# GrandBoard.net
KiCad netlist of a schematic drawn in EAGLE
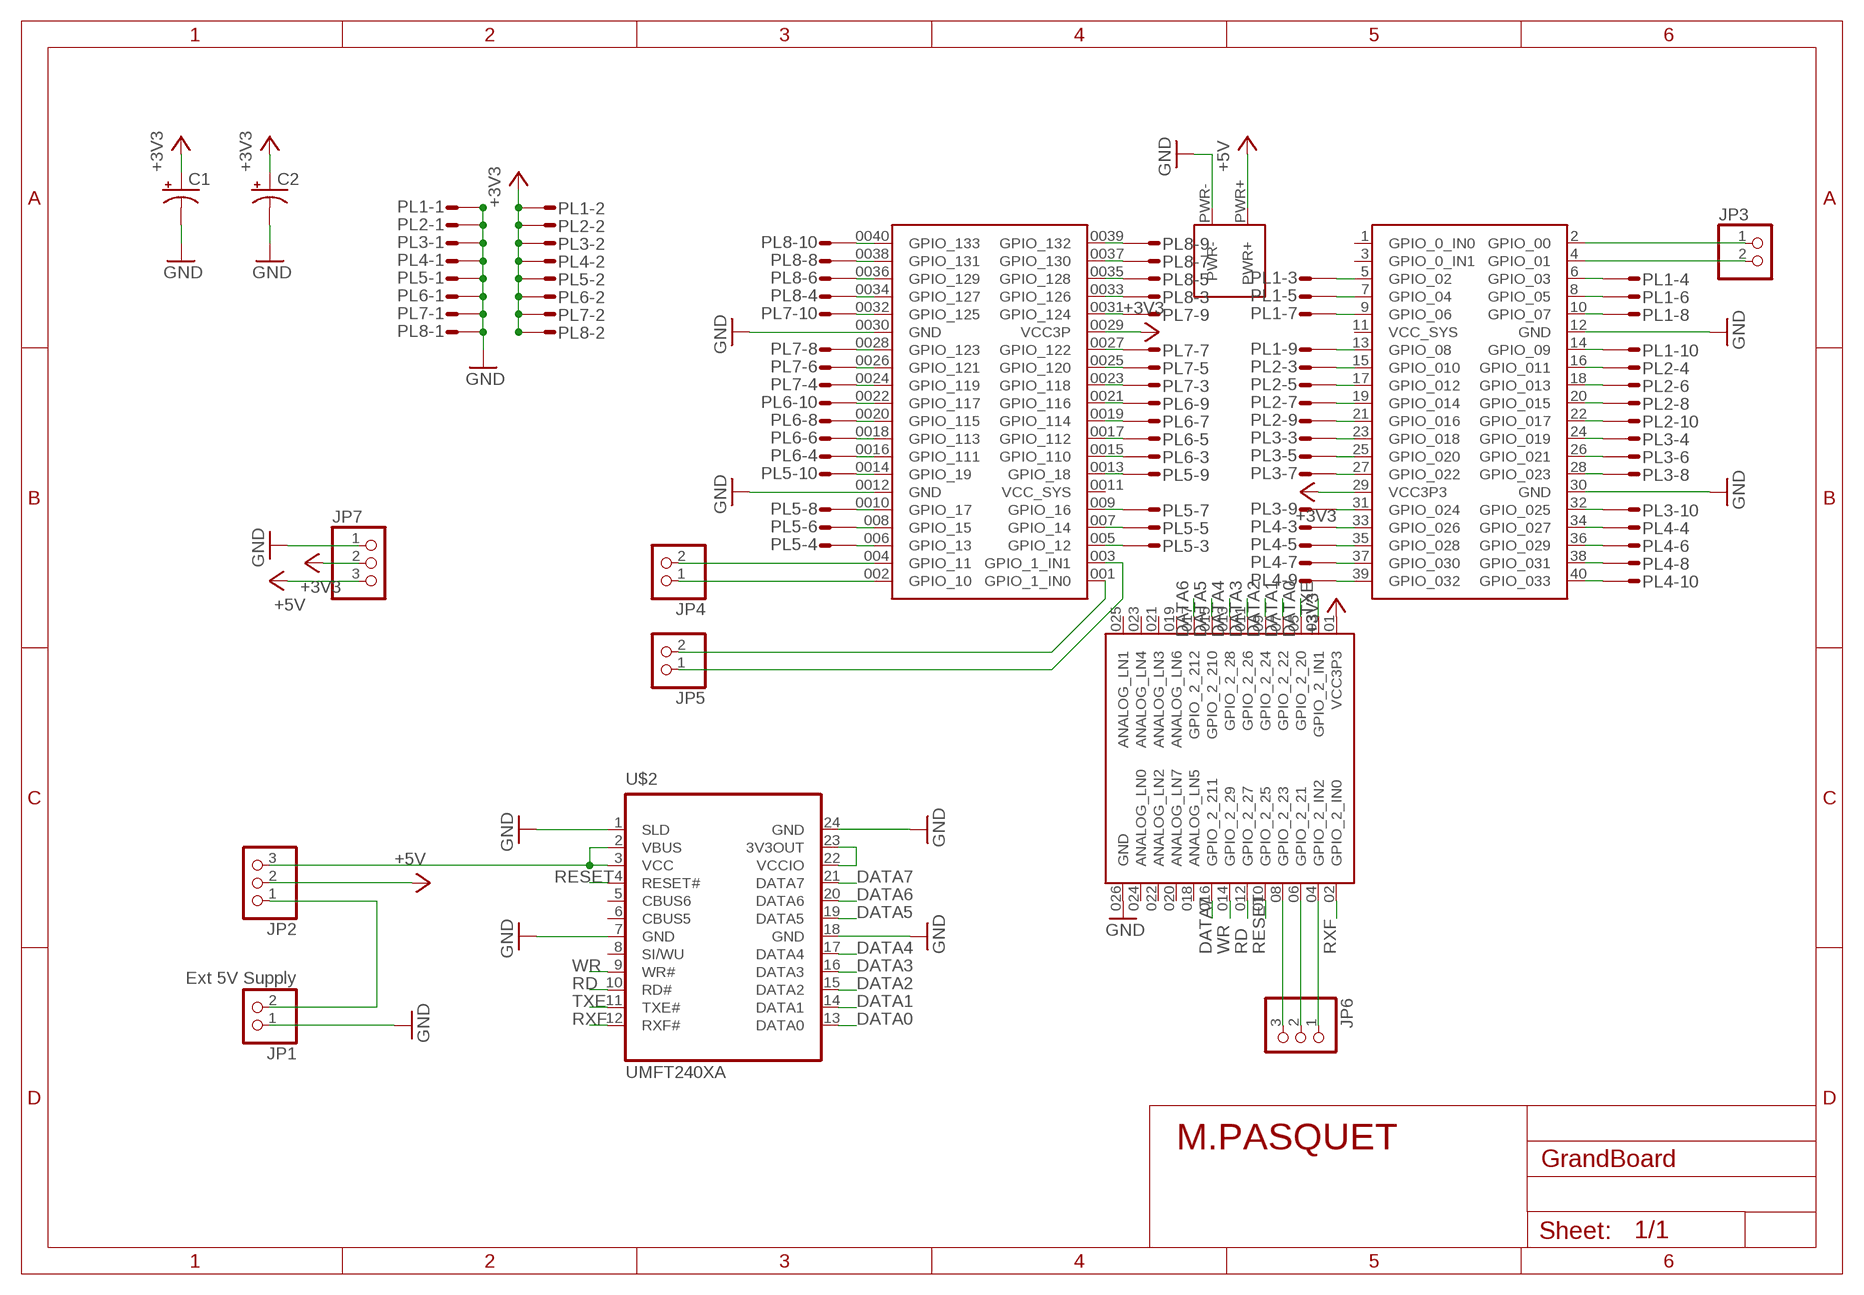
[diagram p0: schematic, sheet 1]

(export (version "E")
  (design (tool "Eeschema 10.0.6"))
  (components
    (comp (ref "C1")
      (value "CAP_POLPTH2")
      (footprint "eagle-import:CPOL-RADIAL-10UF-25V")
      (libsource (lib "eagle-import") (part "CAP_POLPTH2"))
    )
    (comp (ref "C2")
      (value "CAP_POLPTH2")
      (footprint "eagle-import:CPOL-RADIAL-10UF-25V")
      (libsource (lib "eagle-import") (part "CAP_POLPTH2"))
    )
    (comp (ref "JP1")
      (value "Ext 5V Supply")
      (footprint "eagle-import:1X02")
      (libsource (lib "eagle-import") (part "PINHD-1X2"))
    )
    (comp (ref "JP2")
      (value "PINHD-1X3")
      (footprint "eagle-import:1X03")
      (libsource (lib "eagle-import") (part "PINHD-1X3"))
    )
    (comp (ref "JP3")
      (value "PINHD-1X2")
      (footprint "eagle-import:1X02")
      (libsource (lib "eagle-import") (part "PINHD-1X2"))
    )
    (comp (ref "JP4")
      (value "PINHD-1X2")
      (footprint "eagle-import:1X02")
      (libsource (lib "eagle-import") (part "PINHD-1X2"))
    )
    (comp (ref "JP5")
      (value "PINHD-1X2")
      (footprint "eagle-import:1X02")
      (libsource (lib "eagle-import") (part "PINHD-1X2"))
    )
    (comp (ref "JP6")
      (value "PINHD-1X3")
      (footprint "eagle-import:1X03")
      (libsource (lib "eagle-import") (part "PINHD-1X3"))
    )
    (comp (ref "JP7")
      (value "PINHD-1X3")
      (footprint "eagle-import:1X03")
      (libsource (lib "eagle-import") (part "PINHD-1X3"))
    )
    (comp (ref "PL1")
      (value "10HS")
      (footprint "eagle-import:10H")
      (libsource (lib "eagle-import") (part "10HS"))
    )
    (comp (ref "PL2")
      (value "10HS")
      (footprint "eagle-import:10H")
      (libsource (lib "eagle-import") (part "10HS"))
    )
    (comp (ref "PL3")
      (value "10HS")
      (footprint "eagle-import:10H")
      (libsource (lib "eagle-import") (part "10HS"))
    )
    (comp (ref "PL4")
      (value "10HS")
      (footprint "eagle-import:10H")
      (libsource (lib "eagle-import") (part "10HS"))
    )
    (comp (ref "PL5")
      (value "10HS")
      (footprint "eagle-import:10H")
      (libsource (lib "eagle-import") (part "10HS"))
    )
    (comp (ref "PL6")
      (value "10HS")
      (footprint "eagle-import:10H")
      (libsource (lib "eagle-import") (part "10HS"))
    )
    (comp (ref "PL7")
      (value "10HS")
      (footprint "eagle-import:10H")
      (libsource (lib "eagle-import") (part "10HS"))
    )
    (comp (ref "PL8")
      (value "10HS")
      (footprint "eagle-import:10H")
      (libsource (lib "eagle-import") (part "10HS"))
    )
    (comp (ref "U$1")
      (value "DE0-NANO")
      (footprint "eagle-import:DE0-NANO")
      (libsource (lib "eagle-import") (part "DE0-NANO"))
    )
    (comp (ref "U$2")
      (value "UMFT240XA")
      (footprint "eagle-import:UMFT240XA")
      (libsource (lib "eagle-import") (part "UMFT240XA"))
    )
  )
  (nets
    (net (code "1") (name "+3V3") (class "Default")
      (node (ref "C1") (pin "1") (pinfunction "+_1") (pintype "passive"))
      (node (ref "C2") (pin "1") (pinfunction "+_1") (pintype "passive"))
      (node (ref "JP7") (pin "2") (pinfunction "2_2") (pintype "passive"))
      (node (ref "PL1") (pin "2") (pinfunction "S_2") (pintype "passive"))
      (node (ref "PL2") (pin "2") (pinfunction "S_2") (pintype "passive"))
      (node (ref "PL3") (pin "2") (pinfunction "S_2") (pintype "passive"))
      (node (ref "PL4") (pin "2") (pinfunction "S_2") (pintype "passive"))
      (node (ref "PL5") (pin "2") (pinfunction "S_2") (pintype "passive"))
      (node (ref "PL6") (pin "2") (pinfunction "S_2") (pintype "passive"))
      (node (ref "PL7") (pin "2") (pinfunction "S_2") (pintype "passive"))
      (node (ref "PL8") (pin "2") (pinfunction "S_2") (pintype "passive"))
      (node (ref "U$1") (pin "0029") (pinfunction "VCC3P_0029") (pintype "bidirectional"))
      (node (ref "U$1") (pin "01") (pinfunction "VCC3P3_01") (pintype "bidirectional"))
      (node (ref "U$1") (pin "29") (pinfunction "VCC3P3_29") (pintype "bidirectional"))
    )
    (net (code "2") (name "+5V") (class "Default")
      (node (ref "JP2") (pin "2") (pinfunction "2_2") (pintype "passive"))
      (node (ref "JP7") (pin "3") (pinfunction "3_3") (pintype "passive"))
      (node (ref "U$1") (pin "PWR+") (pinfunction "PWR+_PWR+") (pintype "bidirectional"))
    )
    (net (code "3") (name "/DATA0") (class "Default")
      (node (ref "U$1") (pin "05") (pinfunction "GPIO_2_20_05") (pintype "bidirectional"))
      (node (ref "U$2") (pin "13") (pinfunction "DATA0_13") (pintype "input"))
    )
    (net (code "4") (name "/DATA1") (class "Default")
      (node (ref "U$1") (pin "07") (pinfunction "GPIO_2_22_07") (pintype "bidirectional"))
      (node (ref "U$2") (pin "14") (pinfunction "DATA1_14") (pintype "input"))
    )
    (net (code "5") (name "/DATA2") (class "Default")
      (node (ref "U$1") (pin "09") (pinfunction "GPIO_2_24_09") (pintype "bidirectional"))
      (node (ref "U$2") (pin "15") (pinfunction "DATA2_15") (pintype "input"))
    )
    (net (code "6") (name "/DATA3") (class "Default")
      (node (ref "U$1") (pin "011") (pinfunction "GPIO_2_26_011") (pintype "bidirectional"))
      (node (ref "U$2") (pin "16") (pinfunction "DATA3_16") (pintype "input"))
    )
    (net (code "7") (name "/DATA4") (class "Default")
      (node (ref "U$1") (pin "013") (pinfunction "GPIO_2_28_013") (pintype "bidirectional"))
      (node (ref "U$2") (pin "17") (pinfunction "DATA4_17") (pintype "input"))
    )
    (net (code "8") (name "/DATA5") (class "Default")
      (node (ref "U$1") (pin "015") (pinfunction "GPIO_2_210_015") (pintype "bidirectional"))
      (node (ref "U$2") (pin "19") (pinfunction "DATA5_19") (pintype "input"))
    )
    (net (code "9") (name "/DATA6") (class "Default")
      (node (ref "U$1") (pin "017") (pinfunction "GPIO_2_212_017") (pintype "bidirectional"))
      (node (ref "U$2") (pin "20") (pinfunction "DATA6_20") (pintype "input"))
    )
    (net (code "10") (name "/DATA7") (class "Default")
      (node (ref "U$1") (pin "016") (pinfunction "GPIO_2_211_016") (pintype "bidirectional"))
      (node (ref "U$2") (pin "21") (pinfunction "DATA7_21") (pintype "input"))
    )
    (net (code "11") (name "/RD") (class "Default")
      (node (ref "U$1") (pin "012") (pinfunction "GPIO_2_27_012") (pintype "bidirectional"))
      (node (ref "U$2") (pin "10") (pinfunction "RD#_10") (pintype "input"))
    )
    (net (code "12") (name "/RESET") (class "Default")
      (node (ref "U$1") (pin "010") (pinfunction "GPIO_2_25_010") (pintype "bidirectional"))
      (node (ref "U$2") (pin "4") (pinfunction "RESET#_4") (pintype "input"))
    )
    (net (code "13") (name "/RXF") (class "Default")
      (node (ref "U$1") (pin "02") (pinfunction "GPIO_2_IN0_02") (pintype "bidirectional"))
      (node (ref "U$2") (pin "12") (pinfunction "RXF#_12") (pintype "input"))
    )
    (net (code "14") (name "/TXE") (class "Default")
      (node (ref "U$1") (pin "03") (pinfunction "GPIO_2_IN1_03") (pintype "bidirectional"))
      (node (ref "U$2") (pin "11") (pinfunction "TXE#_11") (pintype "input"))
    )
    (net (code "15") (name "/WR") (class "Default")
      (node (ref "U$1") (pin "014") (pinfunction "GPIO_2_29_014") (pintype "bidirectional"))
      (node (ref "U$2") (pin "9") (pinfunction "WR#_9") (pintype "input"))
    )
    (net (code "16") (name "GND") (class "Default")
      (node (ref "C1") (pin "2") (pinfunction "-_2") (pintype "passive"))
      (node (ref "C2") (pin "2") (pinfunction "-_2") (pintype "passive"))
      (node (ref "JP1") (pin "1") (pinfunction "1_1") (pintype "passive"))
      (node (ref "JP7") (pin "1") (pinfunction "1_1") (pintype "passive"))
      (node (ref "PL1") (pin "1") (pinfunction "S_1") (pintype "passive"))
      (node (ref "PL2") (pin "1") (pinfunction "S_1") (pintype "passive"))
      (node (ref "PL3") (pin "1") (pinfunction "S_1") (pintype "passive"))
      (node (ref "PL4") (pin "1") (pinfunction "S_1") (pintype "passive"))
      (node (ref "PL5") (pin "1") (pinfunction "S_1") (pintype "passive"))
      (node (ref "PL6") (pin "1") (pinfunction "S_1") (pintype "passive"))
      (node (ref "PL7") (pin "1") (pinfunction "S_1") (pintype "passive"))
      (node (ref "PL8") (pin "1") (pinfunction "S_1") (pintype "passive"))
      (node (ref "U$1") (pin "0012") (pinfunction "GND_0012") (pintype "bidirectional"))
      (node (ref "U$1") (pin "0030") (pinfunction "GND_0030") (pintype "bidirectional"))
      (node (ref "U$1") (pin "026") (pinfunction "GND_026") (pintype "bidirectional"))
      (node (ref "U$1") (pin "12") (pinfunction "GND_12") (pintype "bidirectional"))
      (node (ref "U$1") (pin "30") (pinfunction "GND_30") (pintype "bidirectional"))
      (node (ref "U$1") (pin "PWR-") (pinfunction "PWR-_PWR-") (pintype "bidirectional"))
      (node (ref "U$2") (pin "1") (pinfunction "SLD_1") (pintype "input"))
      (node (ref "U$2") (pin "18") (pinfunction "GND_18") (pintype "input"))
      (node (ref "U$2") (pin "24") (pinfunction "GND_24") (pintype "input"))
      (node (ref "U$2") (pin "7") (pinfunction "GND_7") (pintype "input"))
    )
    (net (code "17") (name "Net-(JP1-Pad2)") (class "Default")
      (node (ref "JP1") (pin "2") (pinfunction "2_2") (pintype "passive"))
      (node (ref "JP2") (pin "1") (pinfunction "1_1") (pintype "passive"))
    )
    (net (code "18") (name "Net-(PL1B-S)") (class "Default")
      (node (ref "PL1") (pin "10") (pinfunction "S_10") (pintype "passive"))
      (node (ref "U$1") (pin "14") (pinfunction "GPIO_09_14") (pintype "bidirectional"))
    )
    (net (code "19") (name "Net-(PL1D-S)") (class "Default")
      (node (ref "PL1") (pin "3") (pinfunction "S_3") (pintype "passive"))
      (node (ref "U$1") (pin "5") (pinfunction "GPIO_02_5") (pintype "bidirectional"))
    )
    (net (code "20") (name "Net-(PL1E-S)") (class "Default")
      (node (ref "PL1") (pin "4") (pinfunction "S_4") (pintype "passive"))
      (node (ref "U$1") (pin "6") (pinfunction "GPIO_03_6") (pintype "bidirectional"))
    )
    (net (code "21") (name "Net-(PL1F-S)") (class "Default")
      (node (ref "PL1") (pin "5") (pinfunction "S_5") (pintype "passive"))
      (node (ref "U$1") (pin "7") (pinfunction "GPIO_04_7") (pintype "bidirectional"))
    )
    (net (code "22") (name "Net-(PL1G-S)") (class "Default")
      (node (ref "PL1") (pin "6") (pinfunction "S_6") (pintype "passive"))
      (node (ref "U$1") (pin "8") (pinfunction "GPIO_05_8") (pintype "bidirectional"))
    )
    (net (code "23") (name "Net-(PL1H-S)") (class "Default")
      (node (ref "PL1") (pin "7") (pinfunction "S_7") (pintype "passive"))
      (node (ref "U$1") (pin "9") (pinfunction "GPIO_06_9") (pintype "bidirectional"))
    )
    (net (code "24") (name "Net-(PL1I-S)") (class "Default")
      (node (ref "PL1") (pin "8") (pinfunction "S_8") (pintype "passive"))
      (node (ref "U$1") (pin "10") (pinfunction "GPIO_07_10") (pintype "bidirectional"))
    )
    (net (code "25") (name "Net-(PL1J-S)") (class "Default")
      (node (ref "PL1") (pin "9") (pinfunction "S_9") (pintype "passive"))
      (node (ref "U$1") (pin "13") (pinfunction "GPIO_08_13") (pintype "bidirectional"))
    )
    (net (code "26") (name "Net-(PL2B-S)") (class "Default")
      (node (ref "PL2") (pin "10") (pinfunction "S_10") (pintype "passive"))
      (node (ref "U$1") (pin "22") (pinfunction "GPIO_017_22") (pintype "bidirectional"))
    )
    (net (code "27") (name "Net-(PL2D-S)") (class "Default")
      (node (ref "PL2") (pin "3") (pinfunction "S_3") (pintype "passive"))
      (node (ref "U$1") (pin "15") (pinfunction "GPIO_010_15") (pintype "bidirectional"))
    )
    (net (code "28") (name "Net-(PL2E-S)") (class "Default")
      (node (ref "PL2") (pin "4") (pinfunction "S_4") (pintype "passive"))
      (node (ref "U$1") (pin "16") (pinfunction "GPIO_011_16") (pintype "bidirectional"))
    )
    (net (code "29") (name "Net-(PL2F-S)") (class "Default")
      (node (ref "PL2") (pin "5") (pinfunction "S_5") (pintype "passive"))
      (node (ref "U$1") (pin "17") (pinfunction "GPIO_012_17") (pintype "bidirectional"))
    )
    (net (code "30") (name "Net-(PL2G-S)") (class "Default")
      (node (ref "PL2") (pin "6") (pinfunction "S_6") (pintype "passive"))
      (node (ref "U$1") (pin "18") (pinfunction "GPIO_013_18") (pintype "bidirectional"))
    )
    (net (code "31") (name "Net-(PL2H-S)") (class "Default")
      (node (ref "PL2") (pin "7") (pinfunction "S_7") (pintype "passive"))
      (node (ref "U$1") (pin "19") (pinfunction "GPIO_014_19") (pintype "bidirectional"))
    )
    (net (code "32") (name "Net-(PL2I-S)") (class "Default")
      (node (ref "PL2") (pin "8") (pinfunction "S_8") (pintype "passive"))
      (node (ref "U$1") (pin "20") (pinfunction "GPIO_015_20") (pintype "bidirectional"))
    )
    (net (code "33") (name "Net-(PL2J-S)") (class "Default")
      (node (ref "PL2") (pin "9") (pinfunction "S_9") (pintype "passive"))
      (node (ref "U$1") (pin "21") (pinfunction "GPIO_016_21") (pintype "bidirectional"))
    )
    (net (code "34") (name "Net-(PL3B-S)") (class "Default")
      (node (ref "PL3") (pin "10") (pinfunction "S_10") (pintype "passive"))
      (node (ref "U$1") (pin "32") (pinfunction "GPIO_025_32") (pintype "bidirectional"))
    )
    (net (code "35") (name "Net-(PL3D-S)") (class "Default")
      (node (ref "PL3") (pin "3") (pinfunction "S_3") (pintype "passive"))
      (node (ref "U$1") (pin "23") (pinfunction "GPIO_018_23") (pintype "bidirectional"))
    )
    (net (code "36") (name "Net-(PL3E-S)") (class "Default")
      (node (ref "PL3") (pin "4") (pinfunction "S_4") (pintype "passive"))
      (node (ref "U$1") (pin "24") (pinfunction "GPIO_019_24") (pintype "bidirectional"))
    )
    (net (code "37") (name "Net-(PL3F-S)") (class "Default")
      (node (ref "PL3") (pin "5") (pinfunction "S_5") (pintype "passive"))
      (node (ref "U$1") (pin "25") (pinfunction "GPIO_020_25") (pintype "bidirectional"))
    )
    (net (code "38") (name "Net-(PL3G-S)") (class "Default")
      (node (ref "PL3") (pin "6") (pinfunction "S_6") (pintype "passive"))
      (node (ref "U$1") (pin "26") (pinfunction "GPIO_021_26") (pintype "bidirectional"))
    )
    (net (code "39") (name "Net-(PL3H-S)") (class "Default")
      (node (ref "PL3") (pin "7") (pinfunction "S_7") (pintype "passive"))
      (node (ref "U$1") (pin "27") (pinfunction "GPIO_022_27") (pintype "bidirectional"))
    )
    (net (code "40") (name "Net-(PL3I-S)") (class "Default")
      (node (ref "PL3") (pin "8") (pinfunction "S_8") (pintype "passive"))
      (node (ref "U$1") (pin "28") (pinfunction "GPIO_023_28") (pintype "bidirectional"))
    )
    (net (code "41") (name "Net-(PL3J-S)") (class "Default")
      (node (ref "PL3") (pin "9") (pinfunction "S_9") (pintype "passive"))
      (node (ref "U$1") (pin "31") (pinfunction "GPIO_024_31") (pintype "bidirectional"))
    )
    (net (code "42") (name "Net-(PL4B-S)") (class "Default")
      (node (ref "PL4") (pin "10") (pinfunction "S_10") (pintype "passive"))
      (node (ref "U$1") (pin "40") (pinfunction "GPIO_033_40") (pintype "bidirectional"))
    )
    (net (code "43") (name "Net-(PL4D-S)") (class "Default")
      (node (ref "PL4") (pin "3") (pinfunction "S_3") (pintype "passive"))
      (node (ref "U$1") (pin "33") (pinfunction "GPIO_026_33") (pintype "bidirectional"))
    )
    (net (code "44") (name "Net-(PL4E-S)") (class "Default")
      (node (ref "PL4") (pin "4") (pinfunction "S_4") (pintype "passive"))
      (node (ref "U$1") (pin "34") (pinfunction "GPIO_027_34") (pintype "bidirectional"))
    )
    (net (code "45") (name "Net-(PL4F-S)") (class "Default")
      (node (ref "PL4") (pin "5") (pinfunction "S_5") (pintype "passive"))
      (node (ref "U$1") (pin "35") (pinfunction "GPIO_028_35") (pintype "bidirectional"))
    )
    (net (code "46") (name "Net-(PL4G-S)") (class "Default")
      (node (ref "PL4") (pin "6") (pinfunction "S_6") (pintype "passive"))
      (node (ref "U$1") (pin "36") (pinfunction "GPIO_029_36") (pintype "bidirectional"))
    )
    (net (code "47") (name "Net-(PL4H-S)") (class "Default")
      (node (ref "PL4") (pin "7") (pinfunction "S_7") (pintype "passive"))
      (node (ref "U$1") (pin "37") (pinfunction "GPIO_030_37") (pintype "bidirectional"))
    )
    (net (code "48") (name "Net-(PL4I-S)") (class "Default")
      (node (ref "PL4") (pin "8") (pinfunction "S_8") (pintype "passive"))
      (node (ref "U$1") (pin "38") (pinfunction "GPIO_031_38") (pintype "bidirectional"))
    )
    (net (code "49") (name "Net-(PL4J-S)") (class "Default")
      (node (ref "PL4") (pin "9") (pinfunction "S_9") (pintype "passive"))
      (node (ref "U$1") (pin "39") (pinfunction "GPIO_032_39") (pintype "bidirectional"))
    )
    (net (code "50") (name "Net-(PL5B-S)") (class "Default")
      (node (ref "PL5") (pin "10") (pinfunction "S_10") (pintype "passive"))
      (node (ref "U$1") (pin "0014") (pinfunction "GPIO_19_0014") (pintype "bidirectional"))
    )
    (net (code "51") (name "Net-(PL5D-S)") (class "Default")
      (node (ref "PL5") (pin "3") (pinfunction "S_3") (pintype "passive"))
      (node (ref "U$1") (pin "005") (pinfunction "GPIO_12_005") (pintype "bidirectional"))
    )
    (net (code "52") (name "Net-(PL5E-S)") (class "Default")
      (node (ref "PL5") (pin "4") (pinfunction "S_4") (pintype "passive"))
      (node (ref "U$1") (pin "006") (pinfunction "GPIO_13_006") (pintype "bidirectional"))
    )
    (net (code "53") (name "Net-(PL5F-S)") (class "Default")
      (node (ref "PL5") (pin "5") (pinfunction "S_5") (pintype "passive"))
      (node (ref "U$1") (pin "007") (pinfunction "GPIO_14_007") (pintype "bidirectional"))
    )
    (net (code "54") (name "Net-(PL5G-S)") (class "Default")
      (node (ref "PL5") (pin "6") (pinfunction "S_6") (pintype "passive"))
      (node (ref "U$1") (pin "008") (pinfunction "GPIO_15_008") (pintype "bidirectional"))
    )
    (net (code "55") (name "Net-(PL5H-S)") (class "Default")
      (node (ref "PL5") (pin "7") (pinfunction "S_7") (pintype "passive"))
      (node (ref "U$1") (pin "009") (pinfunction "GPIO_16_009") (pintype "bidirectional"))
    )
    (net (code "56") (name "Net-(PL5I-S)") (class "Default")
      (node (ref "PL5") (pin "8") (pinfunction "S_8") (pintype "passive"))
      (node (ref "U$1") (pin "0010") (pinfunction "GPIO_17_0010") (pintype "bidirectional"))
    )
    (net (code "57") (name "Net-(PL5J-S)") (class "Default")
      (node (ref "PL5") (pin "9") (pinfunction "S_9") (pintype "passive"))
      (node (ref "U$1") (pin "0013") (pinfunction "GPIO_18_0013") (pintype "bidirectional"))
    )
    (net (code "58") (name "Net-(PL6B-S)") (class "Default")
      (node (ref "PL6") (pin "10") (pinfunction "S_10") (pintype "passive"))
      (node (ref "U$1") (pin "0022") (pinfunction "GPIO_117_0022") (pintype "bidirectional"))
    )
    (net (code "59") (name "Net-(PL6D-S)") (class "Default")
      (node (ref "PL6") (pin "3") (pinfunction "S_3") (pintype "passive"))
      (node (ref "U$1") (pin "0015") (pinfunction "GPIO_110_0015") (pintype "bidirectional"))
    )
    (net (code "60") (name "Net-(PL6E-S)") (class "Default")
      (node (ref "PL6") (pin "4") (pinfunction "S_4") (pintype "passive"))
      (node (ref "U$1") (pin "0016") (pinfunction "GPIO_111_0016") (pintype "bidirectional"))
    )
    (net (code "61") (name "Net-(PL6F-S)") (class "Default")
      (node (ref "PL6") (pin "5") (pinfunction "S_5") (pintype "passive"))
      (node (ref "U$1") (pin "0017") (pinfunction "GPIO_112_0017") (pintype "bidirectional"))
    )
    (net (code "62") (name "Net-(PL6G-S)") (class "Default")
      (node (ref "PL6") (pin "6") (pinfunction "S_6") (pintype "passive"))
      (node (ref "U$1") (pin "0018") (pinfunction "GPIO_113_0018") (pintype "bidirectional"))
    )
    (net (code "63") (name "Net-(PL6H-S)") (class "Default")
      (node (ref "PL6") (pin "7") (pinfunction "S_7") (pintype "passive"))
      (node (ref "U$1") (pin "0019") (pinfunction "GPIO_114_0019") (pintype "bidirectional"))
    )
    (net (code "64") (name "Net-(PL6I-S)") (class "Default")
      (node (ref "PL6") (pin "8") (pinfunction "S_8") (pintype "passive"))
      (node (ref "U$1") (pin "0020") (pinfunction "GPIO_115_0020") (pintype "bidirectional"))
    )
    (net (code "65") (name "Net-(PL6J-S)") (class "Default")
      (node (ref "PL6") (pin "9") (pinfunction "S_9") (pintype "passive"))
      (node (ref "U$1") (pin "0021") (pinfunction "GPIO_116_0021") (pintype "bidirectional"))
    )
    (net (code "66") (name "Net-(PL7B-S)") (class "Default")
      (node (ref "PL7") (pin "10") (pinfunction "S_10") (pintype "passive"))
      (node (ref "U$1") (pin "0032") (pinfunction "GPIO_125_0032") (pintype "bidirectional"))
    )
    (net (code "67") (name "Net-(PL7D-S)") (class "Default")
      (node (ref "PL7") (pin "3") (pinfunction "S_3") (pintype "passive"))
      (node (ref "U$1") (pin "0023") (pinfunction "GPIO_118_0023") (pintype "bidirectional"))
    )
    (net (code "68") (name "Net-(PL7E-S)") (class "Default")
      (node (ref "PL7") (pin "4") (pinfunction "S_4") (pintype "passive"))
      (node (ref "U$1") (pin "0024") (pinfunction "GPIO_119_0024") (pintype "bidirectional"))
    )
    (net (code "69") (name "Net-(PL7F-S)") (class "Default")
      (node (ref "PL7") (pin "5") (pinfunction "S_5") (pintype "passive"))
      (node (ref "U$1") (pin "0025") (pinfunction "GPIO_120_0025") (pintype "bidirectional"))
    )
    (net (code "70") (name "Net-(PL7G-S)") (class "Default")
      (node (ref "PL7") (pin "6") (pinfunction "S_6") (pintype "passive"))
      (node (ref "U$1") (pin "0026") (pinfunction "GPIO_121_0026") (pintype "bidirectional"))
    )
    (net (code "71") (name "Net-(PL7H-S)") (class "Default")
      (node (ref "PL7") (pin "7") (pinfunction "S_7") (pintype "passive"))
      (node (ref "U$1") (pin "0027") (pinfunction "GPIO_122_0027") (pintype "bidirectional"))
    )
    (net (code "72") (name "Net-(PL7I-S)") (class "Default")
      (node (ref "PL7") (pin "8") (pinfunction "S_8") (pintype "passive"))
      (node (ref "U$1") (pin "0028") (pinfunction "GPIO_123_0028") (pintype "bidirectional"))
    )
    (net (code "73") (name "Net-(PL7J-S)") (class "Default")
      (node (ref "PL7") (pin "9") (pinfunction "S_9") (pintype "passive"))
      (node (ref "U$1") (pin "0031") (pinfunction "GPIO_124_0031") (pintype "bidirectional"))
    )
    (net (code "74") (name "Net-(PL8B-S)") (class "Default")
      (node (ref "PL8") (pin "10") (pinfunction "S_10") (pintype "passive"))
      (node (ref "U$1") (pin "0040") (pinfunction "GPIO_133_0040") (pintype "bidirectional"))
    )
    (net (code "75") (name "Net-(PL8D-S)") (class "Default")
      (node (ref "PL8") (pin "3") (pinfunction "S_3") (pintype "passive"))
      (node (ref "U$1") (pin "0033") (pinfunction "GPIO_126_0033") (pintype "bidirectional"))
    )
    (net (code "76") (name "Net-(PL8E-S)") (class "Default")
      (node (ref "PL8") (pin "4") (pinfunction "S_4") (pintype "passive"))
      (node (ref "U$1") (pin "0034") (pinfunction "GPIO_127_0034") (pintype "bidirectional"))
    )
    (net (code "77") (name "Net-(PL8F-S)") (class "Default")
      (node (ref "PL8") (pin "5") (pinfunction "S_5") (pintype "passive"))
      (node (ref "U$1") (pin "0035") (pinfunction "GPIO_128_0035") (pintype "bidirectional"))
    )
    (net (code "78") (name "Net-(PL8G-S)") (class "Default")
      (node (ref "PL8") (pin "6") (pinfunction "S_6") (pintype "passive"))
      (node (ref "U$1") (pin "0036") (pinfunction "GPIO_129_0036") (pintype "bidirectional"))
    )
    (net (code "79") (name "Net-(PL8H-S)") (class "Default")
      (node (ref "PL8") (pin "7") (pinfunction "S_7") (pintype "passive"))
      (node (ref "U$1") (pin "0037") (pinfunction "GPIO_130_0037") (pintype "bidirectional"))
    )
    (net (code "80") (name "Net-(PL8I-S)") (class "Default")
      (node (ref "PL8") (pin "8") (pinfunction "S_8") (pintype "passive"))
      (node (ref "U$1") (pin "0038") (pinfunction "GPIO_131_0038") (pintype "bidirectional"))
    )
    (net (code "81") (name "Net-(PL8J-S)") (class "Default")
      (node (ref "PL8") (pin "9") (pinfunction "S_9") (pintype "passive"))
      (node (ref "U$1") (pin "0039") (pinfunction "GPIO_132_0039") (pintype "bidirectional"))
    )
    (net (code "82") (name "Net-(U$1-GPIO_00)") (class "Default")
      (node (ref "JP3") (pin "1") (pinfunction "1_1") (pintype "passive"))
      (node (ref "U$1") (pin "2") (pinfunction "GPIO_00_2") (pintype "bidirectional"))
    )
    (net (code "83") (name "Net-(U$1-GPIO_01)") (class "Default")
      (node (ref "JP3") (pin "2") (pinfunction "2_2") (pintype "passive"))
      (node (ref "U$1") (pin "4") (pinfunction "GPIO_01_4") (pintype "bidirectional"))
    )
    (net (code "84") (name "Net-(U$1-GPIO_1_IN0)") (class "Default")
      (node (ref "JP5") (pin "2") (pinfunction "2_2") (pintype "passive"))
      (node (ref "U$1") (pin "001") (pinfunction "GPIO_1_IN0_001") (pintype "bidirectional"))
    )
    (net (code "85") (name "Net-(U$1-GPIO_1_IN1)") (class "Default")
      (node (ref "JP5") (pin "1") (pinfunction "1_1") (pintype "passive"))
      (node (ref "U$1") (pin "003") (pinfunction "GPIO_1_IN1_003") (pintype "bidirectional"))
    )
    (net (code "86") (name "Net-(U$1-GPIO_2_21)") (class "Default")
      (node (ref "JP6") (pin "2") (pinfunction "2_2") (pintype "passive"))
      (node (ref "U$1") (pin "06") (pinfunction "GPIO_2_21_06") (pintype "bidirectional"))
    )
    (net (code "87") (name "Net-(U$1-GPIO_2_23)") (class "Default")
      (node (ref "JP6") (pin "3") (pinfunction "3_3") (pintype "passive"))
      (node (ref "U$1") (pin "08") (pinfunction "GPIO_2_23_08") (pintype "bidirectional"))
    )
    (net (code "88") (name "Net-(U$1-GPIO_2_IN2)") (class "Default")
      (node (ref "JP6") (pin "1") (pinfunction "1_1") (pintype "passive"))
      (node (ref "U$1") (pin "04") (pinfunction "GPIO_2_IN2_04") (pintype "bidirectional"))
    )
    (net (code "89") (name "Net-(U$1-GPIO_10)") (class "Default")
      (node (ref "JP4") (pin "1") (pinfunction "1_1") (pintype "passive"))
      (node (ref "U$1") (pin "002") (pinfunction "GPIO_10_002") (pintype "bidirectional"))
    )
    (net (code "90") (name "Net-(U$1-GPIO_11)") (class "Default")
      (node (ref "JP4") (pin "2") (pinfunction "2_2") (pintype "passive"))
      (node (ref "U$1") (pin "004") (pinfunction "GPIO_11_004") (pintype "bidirectional"))
    )
    (net (code "91") (name "Net-(U$2-3V3OUT)") (class "Default")
      (node (ref "U$2") (pin "22") (pinfunction "VCCIO_22") (pintype "input"))
      (node (ref "U$2") (pin "23") (pinfunction "3V3OUT_23") (pintype "input"))
    )
    (net (code "92") (name "Net-(U$2-VBUS)") (class "Default")
      (node (ref "JP2") (pin "3") (pinfunction "3_3") (pintype "passive"))
      (node (ref "U$2") (pin "2") (pinfunction "VBUS_2") (pintype "input"))
      (node (ref "U$2") (pin "3") (pinfunction "VCC_3") (pintype "input"))
    )
    (net (code "93") (name "unconnected-(U$1-ANALOG_LN0-Pad024)") (class "Default")
      (node (ref "U$1") (pin "024") (pinfunction "ANALOG_LN0_024") (pintype "bidirectional"))
    )
    (net (code "94") (name "unconnected-(U$1-ANALOG_LN1-Pad025)") (class "Default")
      (node (ref "U$1") (pin "025") (pinfunction "ANALOG_LN1_025") (pintype "bidirectional"))
    )
    (net (code "95") (name "unconnected-(U$1-ANALOG_LN2-Pad022)") (class "Default")
      (node (ref "U$1") (pin "022") (pinfunction "ANALOG_LN2_022") (pintype "bidirectional"))
    )
    (net (code "96") (name "unconnected-(U$1-ANALOG_LN3-Pad021)") (class "Default")
      (node (ref "U$1") (pin "021") (pinfunction "ANALOG_LN3_021") (pintype "bidirectional"))
    )
    (net (code "97") (name "unconnected-(U$1-ANALOG_LN4-Pad023)") (class "Default")
      (node (ref "U$1") (pin "023") (pinfunction "ANALOG_LN4_023") (pintype "bidirectional"))
    )
    (net (code "98") (name "unconnected-(U$1-ANALOG_LN5-Pad018)") (class "Default")
      (node (ref "U$1") (pin "018") (pinfunction "ANALOG_LN5_018") (pintype "bidirectional"))
    )
    (net (code "99") (name "unconnected-(U$1-ANALOG_LN6-Pad019)") (class "Default")
      (node (ref "U$1") (pin "019") (pinfunction "ANALOG_LN6_019") (pintype "bidirectional"))
    )
    (net (code "100") (name "unconnected-(U$1-ANALOG_LN7-Pad020)") (class "Default")
      (node (ref "U$1") (pin "020") (pinfunction "ANALOG_LN7_020") (pintype "bidirectional"))
    )
    (net (code "101") (name "unconnected-(U$1-GPIO_0_IN0-Pad1)") (class "Default")
      (node (ref "U$1") (pin "1") (pinfunction "GPIO_0_IN0_1") (pintype "bidirectional"))
    )
    (net (code "102") (name "unconnected-(U$1-GPIO_0_IN1-Pad3)") (class "Default")
      (node (ref "U$1") (pin "3") (pinfunction "GPIO_0_IN1_3") (pintype "bidirectional"))
    )
    (net (code "103") (name "unconnected-(U$1-VCC_SYS-Pad11)") (class "Default")
      (node (ref "U$1") (pin "11") (pinfunction "VCC_SYS_11") (pintype "bidirectional"))
    )
    (net (code "104") (name "unconnected-(U$1-VCC_SYS-Pad0011)") (class "Default")
      (node (ref "U$1") (pin "0011") (pinfunction "VCC_SYS_0011") (pintype "bidirectional"))
    )
    (net (code "105") (name "unconnected-(U$2-CBUS5-Pad6)") (class "Default")
      (node (ref "U$2") (pin "6") (pinfunction "CBUS5_6") (pintype "input"))
    )
    (net (code "106") (name "unconnected-(U$2-CBUS6-Pad5)") (class "Default")
      (node (ref "U$2") (pin "5") (pinfunction "CBUS6_5") (pintype "input"))
    )
    (net (code "107") (name "unconnected-(U$2-SI{slash}WU-Pad8)") (class "Default")
      (node (ref "U$2") (pin "8") (pinfunction "SI/WU_8") (pintype "input"))
    )
  )
)
